# Flight_Control_Board.net
KiCad netlist of a schematic drawn in Altium Designer
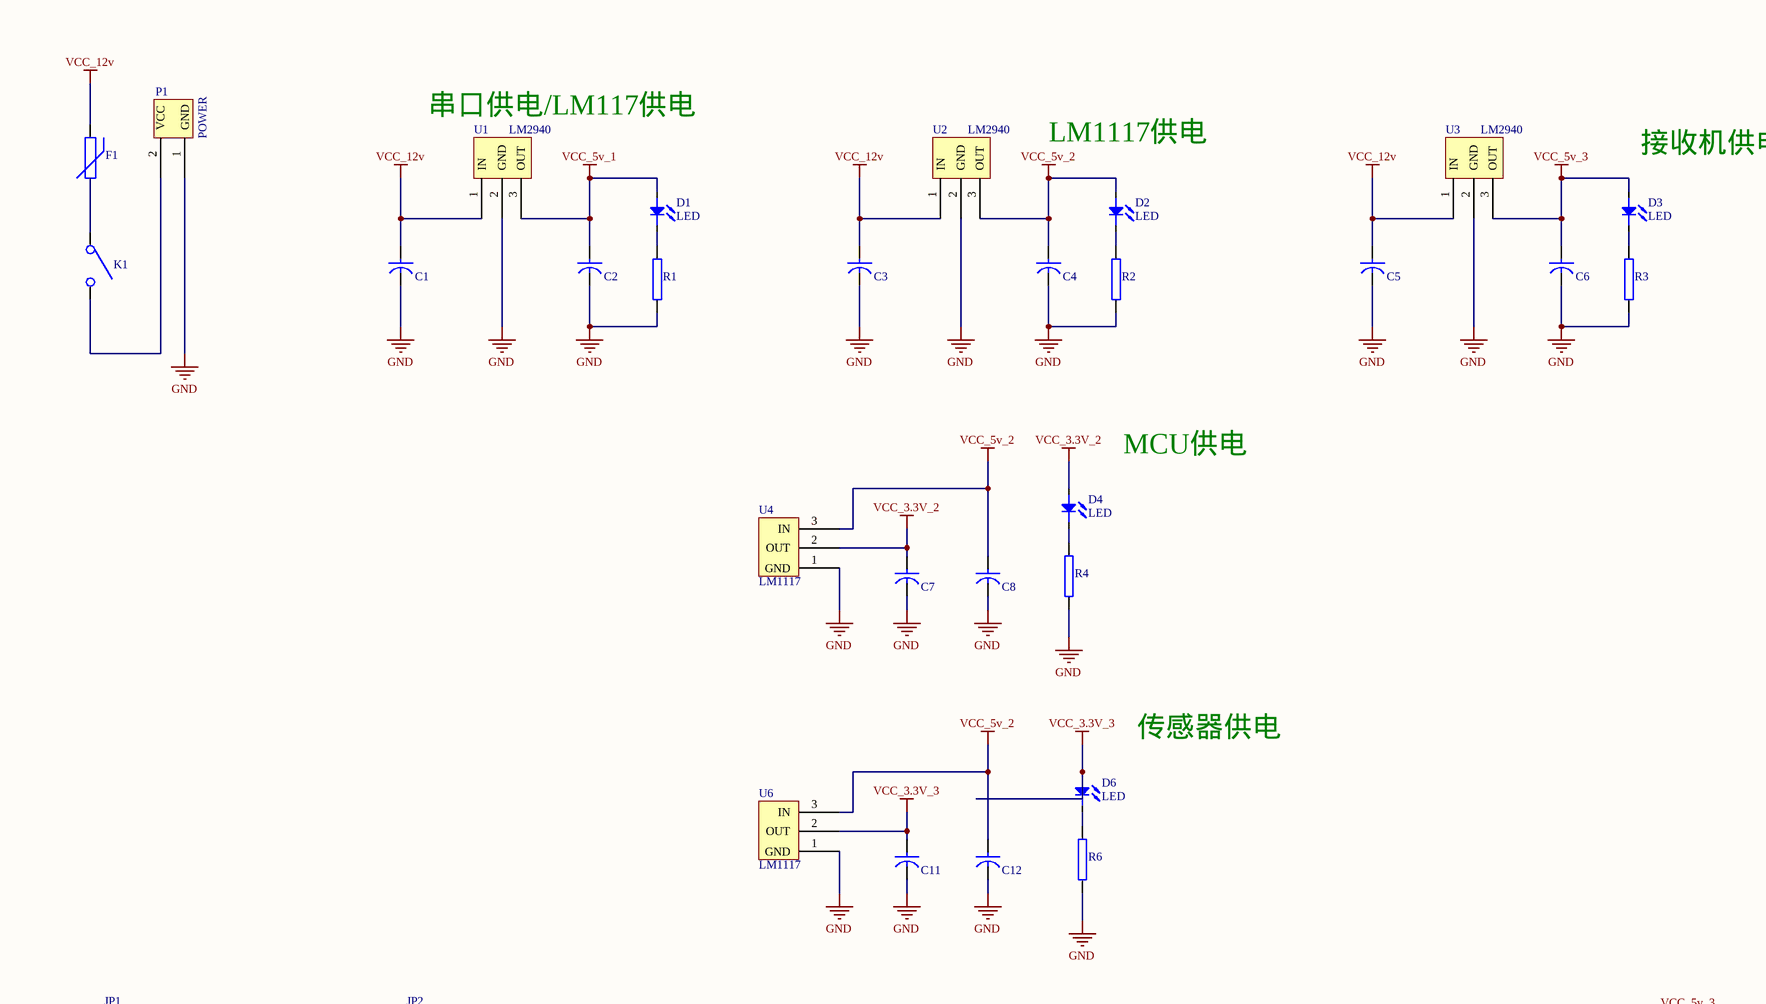
[diagram p0: Flight Control Board.SchDoc, top left]
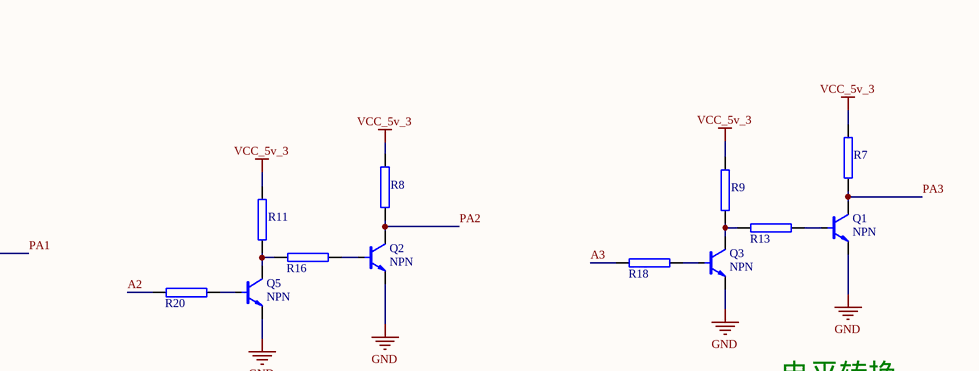
[diagram p1: Flight Control Board.SchDoc, top right]
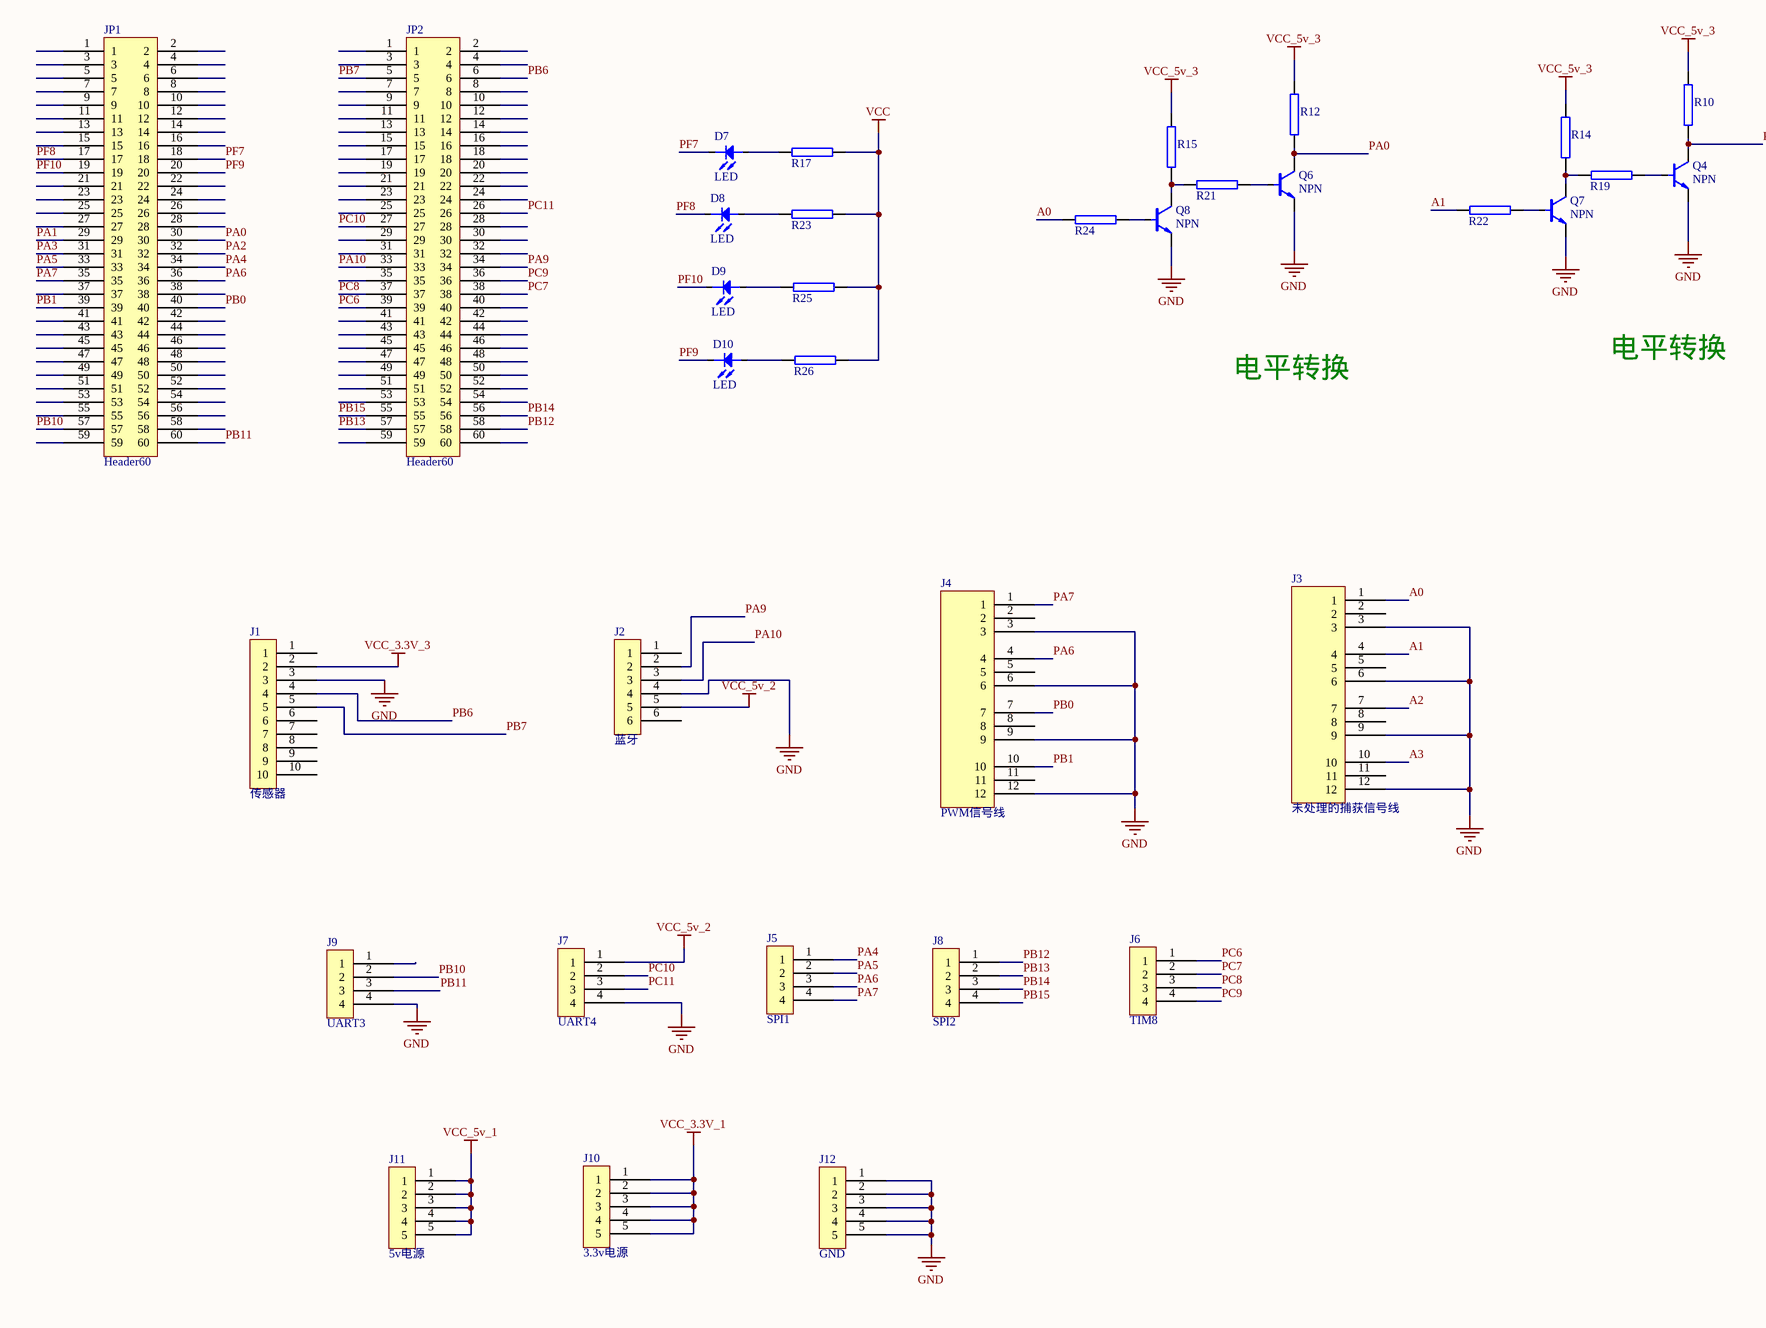
[diagram p2: Flight Control Board.SchDoc, bottom left]
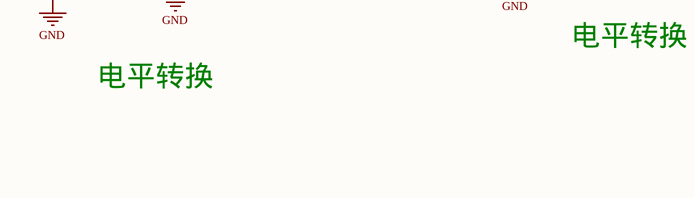
[diagram p3: Flight Control Board.SchDoc, bottom right]

(export (version "E")
  (design (tool "Eeschema 10.0.6"))
  (components
    (comp (ref "C1") (value "CAP_C") (footprint "CAP_C") (libsource (lib "Schlib1") (part "CAP_C")))
    (comp (ref "C2") (value "CAP_C") (footprint "CAP_C") (libsource (lib "Schlib1") (part "CAP_C")))
    (comp (ref "C3") (value "CAP_C") (footprint "CAP_C") (libsource (lib "Schlib1") (part "CAP_C")))
    (comp (ref "C4") (value "CAP_C") (footprint "CAP_C") (libsource (lib "Schlib1") (part "CAP_C")))
    (comp (ref "C5") (value "CAP_C") (footprint "CAP_C") (libsource (lib "Schlib1") (part "CAP_C")))
    (comp (ref "C6") (value "CAP_C") (footprint "CAP_C") (libsource (lib "Schlib1") (part "CAP_C")))
    (comp (ref "C7") (value "CAP_C") (footprint "CAP_C") (libsource (lib "Schlib1") (part "CAP_C")))
    (comp (ref "C8") (value "CAP_C") (footprint "CAP_C") (libsource (lib "Schlib1") (part "CAP_C")))
    (comp (ref "C11") (value "CAP_C") (footprint "CAP_C") (libsource (lib "Schlib1") (part "CAP_C")))
    (comp (ref "C12") (value "CAP_C") (footprint "CAP_C") (libsource (lib "Schlib1") (part "CAP_C")))
    (comp (ref "D1") (value "LED") (footprint "LED") (libsource (lib "Schlib1") (part "LED")))
    (comp (ref "D2") (value "LED") (footprint "LED") (libsource (lib "Schlib1") (part "LED")))
    (comp (ref "D3") (value "LED") (footprint "LED") (libsource (lib "Schlib1") (part "LED")))
    (comp (ref "D4") (value "LED") (footprint "LED") (libsource (lib "Schlib1") (part "LED")))
    (comp (ref "D6") (value "LED") (footprint "LED") (libsource (lib "Schlib1") (part "LED")))
    (comp (ref "D7") (value "LED") (footprint "LED") (libsource (lib "Schlib1") (part "LED")))
    (comp (ref "D8") (value "LED") (footprint "LED") (libsource (lib "Schlib1") (part "LED")))
    (comp (ref "D9") (value "LED") (footprint "LED") (libsource (lib "Schlib1") (part "LED")))
    (comp (ref "D10") (value "LED") (footprint "LED") (libsource (lib "Schlib1") (part "LED")))
    (comp (ref "F1") (value "FUSE") (footprint "FUSE") (libsource (lib "Schlib1") (part "FUSE")))
    (comp (ref "J1") (value "传感器") (footprint "Header10") (libsource (lib "Schlib1") (part "Header10")))
    (comp (ref "J2") (value "蓝牙") (footprint "Header6") (libsource (lib "Schlib1") (part "Header6")))
    (comp (ref "J3")
      (value "未处理的捕获信号线")
      (footprint "Header4*3")
      (libsource (lib "Schlib1") (part "Header4*3"))
    )
    (comp (ref "J4") (value "PWM信号线") (footprint "Header4*3") (libsource (lib "Schlib1") (part "Header4*3")))
    (comp (ref "J5") (value "SPI1") (footprint "Header4") (libsource (lib "Schlib1") (part "Header4")))
    (comp (ref "J6") (value "TIM8") (footprint "Header4") (libsource (lib "Schlib1") (part "Header4")))
    (comp (ref "J7") (value "UART4") (footprint "Header4") (libsource (lib "Schlib1") (part "Header4")))
    (comp (ref "J8") (value "SPI2") (footprint "Header4") (libsource (lib "Schlib1") (part "Header4")))
    (comp (ref "J9") (value "UART3") (footprint "Header4") (libsource (lib "Schlib1") (part "Header4")))
    (comp (ref "J10") (value "3.3v电源") (footprint "Header5") (libsource (lib "Schlib1") (part "Header5")))
    (comp (ref "J11") (value "5v电源") (footprint "Header5") (libsource (lib "Schlib1") (part "Header5")))
    (comp (ref "J12") (value "GND") (footprint "Header5") (libsource (lib "Schlib1") (part "Header5")))
    (comp (ref "JP1") (value "Header60") (footprint "Header60") (libsource (lib "Schlib1") (part "Header60")))
    (comp (ref "JP2") (value "Header60") (footprint "Header60") (libsource (lib "Schlib1") (part "Header60")))
    (comp (ref "K1") (value "KEY") (footprint "KEY") (libsource (lib "Schlib1") (part "KEY")))
    (comp (ref "P1") (value "POWER") (footprint "POWER") (libsource (lib "Schlib1") (part "POWER")))
    (comp (ref "Q1") (value "NPN") (footprint "NPN") (libsource (lib "Schlib1") (part "NPN")))
    (comp (ref "Q2") (value "NPN") (footprint "NPN") (libsource (lib "Schlib1") (part "NPN")))
    (comp (ref "Q3") (value "NPN") (footprint "NPN") (libsource (lib "Schlib1") (part "NPN")))
    (comp (ref "Q4") (value "NPN") (footprint "NPN") (libsource (lib "Schlib1") (part "NPN")))
    (comp (ref "Q5") (value "NPN") (footprint "NPN") (libsource (lib "Schlib1") (part "NPN")))
    (comp (ref "Q6") (value "NPN") (footprint "NPN") (libsource (lib "Schlib1") (part "NPN")))
    (comp (ref "Q7") (value "NPN") (footprint "NPN") (libsource (lib "Schlib1") (part "NPN")))
    (comp (ref "Q8") (value "NPN") (footprint "NPN") (libsource (lib "Schlib1") (part "NPN")))
    (comp (ref "R1") (value "RES") (footprint "LED") (libsource (lib "Schlib1") (part "RES")))
    (comp (ref "R2") (value "RES") (footprint "LED") (libsource (lib "Schlib1") (part "RES")))
    (comp (ref "R3") (value "RES") (footprint "LED") (libsource (lib "Schlib1") (part "RES")))
    (comp (ref "R4") (value "RES") (footprint "LED") (libsource (lib "Schlib1") (part "RES")))
    (comp (ref "R6") (value "RES") (footprint "LED") (libsource (lib "Schlib1") (part "RES")))
    (comp (ref "R7") (value "RES") (footprint "LED") (libsource (lib "Schlib1") (part "RES")))
    (comp (ref "R8") (value "RES") (footprint "LED") (libsource (lib "Schlib1") (part "RES")))
    (comp (ref "R9") (value "RES") (footprint "LED") (libsource (lib "Schlib1") (part "RES")))
    (comp (ref "R10") (value "RES") (footprint "LED") (libsource (lib "Schlib1") (part "RES")))
    (comp (ref "R11") (value "RES") (footprint "LED") (libsource (lib "Schlib1") (part "RES")))
    (comp (ref "R12") (value "RES") (footprint "LED") (libsource (lib "Schlib1") (part "RES")))
    (comp (ref "R13") (value "RES") (footprint "LED") (libsource (lib "Schlib1") (part "RES")))
    (comp (ref "R14") (value "RES") (footprint "LED") (libsource (lib "Schlib1") (part "RES")))
    (comp (ref "R15") (value "RES") (footprint "LED") (libsource (lib "Schlib1") (part "RES")))
    (comp (ref "R16") (value "RES") (footprint "LED") (libsource (lib "Schlib1") (part "RES")))
    (comp (ref "R17") (value "RES") (footprint "LED") (libsource (lib "Schlib1") (part "RES")))
    (comp (ref "R18") (value "RES") (footprint "LED") (libsource (lib "Schlib1") (part "RES")))
    (comp (ref "R19") (value "RES") (footprint "LED") (libsource (lib "Schlib1") (part "RES")))
    (comp (ref "R20") (value "RES") (footprint "LED") (libsource (lib "Schlib1") (part "RES")))
    (comp (ref "R21") (value "RES") (footprint "LED") (libsource (lib "Schlib1") (part "RES")))
    (comp (ref "R22") (value "RES") (footprint "LED") (libsource (lib "Schlib1") (part "RES")))
    (comp (ref "R23") (value "RES") (footprint "LED") (libsource (lib "Schlib1") (part "RES")))
    (comp (ref "R24") (value "RES") (footprint "LED") (libsource (lib "Schlib1") (part "RES")))
    (comp (ref "R25") (value "RES") (footprint "LED") (libsource (lib "Schlib1") (part "RES")))
    (comp (ref "R26") (value "RES") (footprint "LED") (libsource (lib "Schlib1") (part "RES")))
    (comp (ref "U1") (value "LM2940") (footprint "2940") (libsource (lib "Schlib1") (part "LM2940")))
    (comp (ref "U2") (value "LM2940") (footprint "2940") (libsource (lib "Schlib1") (part "LM2940")))
    (comp (ref "U3") (value "LM2940") (footprint "2940") (libsource (lib "Schlib1") (part "LM2940")))
    (comp (ref "U4") (value "LM1117") (footprint "1117") (libsource (lib "Schlib1") (part "LM1117")))
    (comp (ref "U6") (value "LM1117") (footprint "1117") (libsource (lib "Schlib1") (part "LM1117")))
  )
  (nets
    (net (code "1") (name "/A0") (class "Default")
      (node (ref "J3") (pin "1") (pinfunction "1_1") (pintype "passive"))
      (node (ref "R24") (pin "2") (pinfunction "2_2") (pintype "passive"))
    )
    (net (code "2") (name "/A1") (class "Default")
      (node (ref "J3") (pin "4") (pinfunction "4_4") (pintype "passive"))
      (node (ref "R22") (pin "2") (pinfunction "2_2") (pintype "passive"))
    )
    (net (code "3") (name "/A2") (class "Default")
      (node (ref "J3") (pin "7") (pinfunction "7_7") (pintype "passive"))
      (node (ref "R20") (pin "2") (pinfunction "2_2") (pintype "passive"))
    )
    (net (code "4") (name "/A3") (class "Default")
      (node (ref "J3") (pin "10") (pinfunction "10_10") (pintype "passive"))
      (node (ref "R18") (pin "2") (pinfunction "2_2") (pintype "passive"))
    )
    (net (code "5") (name "/PA0") (class "Default")
      (node (ref "JP1") (pin "30") (pinfunction "30_30") (pintype "passive"))
      (node (ref "Q6") (pin "C") (pinfunction "c_C") (pintype "passive"))
      (node (ref "R12") (pin "2") (pinfunction "2_2") (pintype "passive"))
    )
    (net (code "6") (name "/PA1") (class "Default")
      (node (ref "JP1") (pin "29") (pinfunction "29_29") (pintype "passive"))
      (node (ref "Q4") (pin "C") (pinfunction "c_C") (pintype "passive"))
      (node (ref "R10") (pin "2") (pinfunction "2_2") (pintype "passive"))
    )
    (net (code "7") (name "/PA2") (class "Default")
      (node (ref "JP1") (pin "32") (pinfunction "32_32") (pintype "passive"))
      (node (ref "Q2") (pin "C") (pinfunction "c_C") (pintype "passive"))
      (node (ref "R8") (pin "2") (pinfunction "2_2") (pintype "passive"))
    )
    (net (code "8") (name "/PA3") (class "Default")
      (node (ref "JP1") (pin "31") (pinfunction "31_31") (pintype "passive"))
      (node (ref "Q1") (pin "C") (pinfunction "c_C") (pintype "passive"))
      (node (ref "R7") (pin "2") (pinfunction "2_2") (pintype "passive"))
    )
    (net (code "9") (name "/PA4") (class "Default")
      (node (ref "J5") (pin "1") (pinfunction "1_1") (pintype "passive"))
      (node (ref "JP1") (pin "34") (pinfunction "34_34") (pintype "passive"))
    )
    (net (code "10") (name "/PA5") (class "Default")
      (node (ref "J5") (pin "2") (pinfunction "2_2") (pintype "passive"))
      (node (ref "JP1") (pin "33") (pinfunction "33_33") (pintype "passive"))
    )
    (net (code "11") (name "/PA6") (class "Default")
      (node (ref "J4") (pin "4") (pinfunction "4_4") (pintype "passive"))
      (node (ref "J5") (pin "3") (pinfunction "3_3") (pintype "passive"))
      (node (ref "JP1") (pin "36") (pinfunction "36_36") (pintype "passive"))
    )
    (net (code "12") (name "/PA7") (class "Default")
      (node (ref "J4") (pin "1") (pinfunction "1_1") (pintype "passive"))
      (node (ref "J5") (pin "4") (pinfunction "4_4") (pintype "passive"))
      (node (ref "JP1") (pin "35") (pinfunction "35_35") (pintype "passive"))
    )
    (net (code "13") (name "/PA9") (class "Default")
      (node (ref "J2") (pin "2") (pinfunction "2_2") (pintype "passive"))
      (node (ref "JP2") (pin "34") (pinfunction "34_34") (pintype "passive"))
    )
    (net (code "14") (name "/PA10") (class "Default")
      (node (ref "J2") (pin "3") (pinfunction "3_3") (pintype "passive"))
      (node (ref "JP2") (pin "33") (pinfunction "33_33") (pintype "passive"))
    )
    (net (code "15") (name "/PB0") (class "Default")
      (node (ref "J4") (pin "7") (pinfunction "7_7") (pintype "passive"))
      (node (ref "JP1") (pin "40") (pinfunction "40_40") (pintype "passive"))
    )
    (net (code "16") (name "/PB1") (class "Default")
      (node (ref "J4") (pin "10") (pinfunction "10_10") (pintype "passive"))
      (node (ref "JP1") (pin "39") (pinfunction "39_39") (pintype "passive"))
    )
    (net (code "17") (name "/PB6") (class "Default")
      (node (ref "J1") (pin "4") (pinfunction "4_4") (pintype "passive"))
      (node (ref "JP2") (pin "6") (pinfunction "6_6") (pintype "passive"))
    )
    (net (code "18") (name "/PB7") (class "Default")
      (node (ref "J1") (pin "5") (pinfunction "5_5") (pintype "passive"))
      (node (ref "JP2") (pin "5") (pinfunction "5_5") (pintype "passive"))
    )
    (net (code "19") (name "/PB10") (class "Default")
      (node (ref "J9") (pin "2") (pinfunction "2_2") (pintype "passive"))
      (node (ref "JP1") (pin "57") (pinfunction "57_57") (pintype "passive"))
    )
    (net (code "20") (name "/PB11") (class "Default")
      (node (ref "J9") (pin "3") (pinfunction "3_3") (pintype "passive"))
      (node (ref "JP1") (pin "60") (pinfunction "60_60") (pintype "passive"))
    )
    (net (code "21") (name "/PB12") (class "Default")
      (node (ref "J8") (pin "1") (pinfunction "1_1") (pintype "passive"))
      (node (ref "JP2") (pin "58") (pinfunction "58_58") (pintype "passive"))
    )
    (net (code "22") (name "/PB13") (class "Default")
      (node (ref "J8") (pin "2") (pinfunction "2_2") (pintype "passive"))
      (node (ref "JP2") (pin "57") (pinfunction "57_57") (pintype "passive"))
    )
    (net (code "23") (name "/PB14") (class "Default")
      (node (ref "J8") (pin "3") (pinfunction "3_3") (pintype "passive"))
      (node (ref "JP2") (pin "56") (pinfunction "56_56") (pintype "passive"))
    )
    (net (code "24") (name "/PB15") (class "Default")
      (node (ref "J8") (pin "4") (pinfunction "4_4") (pintype "passive"))
      (node (ref "JP2") (pin "55") (pinfunction "55_55") (pintype "passive"))
    )
    (net (code "25") (name "/PC6") (class "Default")
      (node (ref "J6") (pin "1") (pinfunction "1_1") (pintype "passive"))
      (node (ref "JP2") (pin "39") (pinfunction "39_39") (pintype "passive"))
    )
    (net (code "26") (name "/PC7") (class "Default")
      (node (ref "J6") (pin "2") (pinfunction "2_2") (pintype "passive"))
      (node (ref "JP2") (pin "38") (pinfunction "38_38") (pintype "passive"))
    )
    (net (code "27") (name "/PC8") (class "Default")
      (node (ref "J6") (pin "3") (pinfunction "3_3") (pintype "passive"))
      (node (ref "JP2") (pin "37") (pinfunction "37_37") (pintype "passive"))
    )
    (net (code "28") (name "/PC9") (class "Default")
      (node (ref "J6") (pin "4") (pinfunction "4_4") (pintype "passive"))
      (node (ref "JP2") (pin "36") (pinfunction "36_36") (pintype "passive"))
    )
    (net (code "29") (name "/PC10") (class "Default")
      (node (ref "J7") (pin "2") (pinfunction "2_2") (pintype "passive"))
      (node (ref "JP2") (pin "27") (pinfunction "27_27") (pintype "passive"))
    )
    (net (code "30") (name "/PC11") (class "Default")
      (node (ref "J7") (pin "3") (pinfunction "3_3") (pintype "passive"))
      (node (ref "JP2") (pin "26") (pinfunction "26_26") (pintype "passive"))
    )
    (net (code "31") (name "/PF7") (class "Default")
      (node (ref "D7") (pin "2") (pinfunction "2_2") (pintype "passive"))
      (node (ref "JP1") (pin "18") (pinfunction "18_18") (pintype "passive"))
    )
    (net (code "32") (name "/PF8") (class "Default")
      (node (ref "D8") (pin "2") (pinfunction "2_2") (pintype "passive"))
      (node (ref "JP1") (pin "17") (pinfunction "17_17") (pintype "passive"))
    )
    (net (code "33") (name "/PF9") (class "Default")
      (node (ref "D10") (pin "2") (pinfunction "2_2") (pintype "passive"))
      (node (ref "JP1") (pin "20") (pinfunction "20_20") (pintype "passive"))
    )
    (net (code "34") (name "/PF10") (class "Default")
      (node (ref "D9") (pin "2") (pinfunction "2_2") (pintype "passive"))
      (node (ref "JP1") (pin "19") (pinfunction "19_19") (pintype "passive"))
    )
    (net (code "35") (name "GND") (class "Default")
      (node (ref "C1") (pin "2") (pinfunction "2_2") (pintype "passive"))
      (node (ref "C11") (pin "2") (pinfunction "2_2") (pintype "passive"))
      (node (ref "C12") (pin "2") (pinfunction "2_2") (pintype "passive"))
      (node (ref "C2") (pin "2") (pinfunction "2_2") (pintype "passive"))
      (node (ref "C3") (pin "2") (pinfunction "2_2") (pintype "passive"))
      (node (ref "C4") (pin "2") (pinfunction "2_2") (pintype "passive"))
      (node (ref "C5") (pin "2") (pinfunction "2_2") (pintype "passive"))
      (node (ref "C6") (pin "2") (pinfunction "2_2") (pintype "passive"))
      (node (ref "C7") (pin "2") (pinfunction "2_2") (pintype "passive"))
      (node (ref "C8") (pin "2") (pinfunction "2_2") (pintype "passive"))
      (node (ref "J1") (pin "3") (pinfunction "3_3") (pintype "passive"))
      (node (ref "J12") (pin "1") (pinfunction "1_1") (pintype "passive"))
      (node (ref "J12") (pin "2") (pinfunction "2_2") (pintype "passive"))
      (node (ref "J12") (pin "3") (pinfunction "3_3") (pintype "passive"))
      (node (ref "J12") (pin "4") (pinfunction "4_4") (pintype "passive"))
      (node (ref "J12") (pin "5") (pinfunction "5_5") (pintype "passive"))
      (node (ref "J2") (pin "4") (pinfunction "4_4") (pintype "passive"))
      (node (ref "J3") (pin "12") (pinfunction "12_12") (pintype "passive"))
      (node (ref "J3") (pin "3") (pinfunction "3_3") (pintype "passive"))
      (node (ref "J3") (pin "6") (pinfunction "6_6") (pintype "passive"))
      (node (ref "J3") (pin "9") (pinfunction "9_9") (pintype "passive"))
      (node (ref "J4") (pin "12") (pinfunction "12_12") (pintype "passive"))
      (node (ref "J4") (pin "3") (pinfunction "3_3") (pintype "passive"))
      (node (ref "J4") (pin "6") (pinfunction "6_6") (pintype "passive"))
      (node (ref "J4") (pin "9") (pinfunction "9_9") (pintype "passive"))
      (node (ref "J7") (pin "4") (pinfunction "4_4") (pintype "passive"))
      (node (ref "J9") (pin "4") (pinfunction "4_4") (pintype "passive"))
      (node (ref "P1") (pin "1") (pinfunction "GND_1") (pintype "passive"))
      (node (ref "Q1") (pin "E") (pinfunction "e_E") (pintype "passive"))
      (node (ref "Q2") (pin "E") (pinfunction "e_E") (pintype "passive"))
      (node (ref "Q3") (pin "E") (pinfunction "e_E") (pintype "passive"))
      (node (ref "Q4") (pin "E") (pinfunction "e_E") (pintype "passive"))
      (node (ref "Q5") (pin "E") (pinfunction "e_E") (pintype "passive"))
      (node (ref "Q6") (pin "E") (pinfunction "e_E") (pintype "passive"))
      (node (ref "Q7") (pin "E") (pinfunction "e_E") (pintype "passive"))
      (node (ref "Q8") (pin "E") (pinfunction "e_E") (pintype "passive"))
      (node (ref "R1") (pin "1") (pinfunction "1_1") (pintype "passive"))
      (node (ref "R2") (pin "1") (pinfunction "1_1") (pintype "passive"))
      (node (ref "R3") (pin "1") (pinfunction "1_1") (pintype "passive"))
      (node (ref "R4") (pin "1") (pinfunction "1_1") (pintype "passive"))
      (node (ref "R6") (pin "1") (pinfunction "1_1") (pintype "passive"))
      (node (ref "U1") (pin "2") (pinfunction "GND_2") (pintype "passive"))
      (node (ref "U2") (pin "2") (pinfunction "GND_2") (pintype "passive"))
      (node (ref "U3") (pin "2") (pinfunction "GND_2") (pintype "passive"))
      (node (ref "U4") (pin "1") (pinfunction "GND_1") (pintype "passive"))
      (node (ref "U6") (pin "1") (pinfunction "GND_1") (pintype "passive"))
    )
    (net (code "36") (name "Net-(D1-Pad2)") (class "Default")
      (node (ref "D1") (pin "2") (pinfunction "2_2") (pintype "passive"))
      (node (ref "R1") (pin "2") (pinfunction "2_2") (pintype "passive"))
    )
    (net (code "37") (name "Net-(D2-Pad2)") (class "Default")
      (node (ref "D2") (pin "2") (pinfunction "2_2") (pintype "passive"))
      (node (ref "R2") (pin "2") (pinfunction "2_2") (pintype "passive"))
    )
    (net (code "38") (name "Net-(D3-Pad2)") (class "Default")
      (node (ref "D3") (pin "2") (pinfunction "2_2") (pintype "passive"))
      (node (ref "R3") (pin "2") (pinfunction "2_2") (pintype "passive"))
    )
    (net (code "39") (name "Net-(D4-Pad2)") (class "Default")
      (node (ref "D4") (pin "2") (pinfunction "2_2") (pintype "passive"))
      (node (ref "R4") (pin "2") (pinfunction "2_2") (pintype "passive"))
    )
    (net (code "40") (name "Net-(D6-Pad2)") (class "Default")
      (node (ref "D6") (pin "2") (pinfunction "2_2") (pintype "passive"))
      (node (ref "R6") (pin "2") (pinfunction "2_2") (pintype "passive"))
    )
    (net (code "41") (name "Net-(D7-Pad1)") (class "Default")
      (node (ref "D7") (pin "1") (pinfunction "1_1") (pintype "passive"))
      (node (ref "R17") (pin "2") (pinfunction "2_2") (pintype "passive"))
    )
    (net (code "42") (name "Net-(D8-Pad1)") (class "Default")
      (node (ref "D8") (pin "1") (pinfunction "1_1") (pintype "passive"))
      (node (ref "R23") (pin "2") (pinfunction "2_2") (pintype "passive"))
    )
    (net (code "43") (name "Net-(D9-Pad1)") (class "Default")
      (node (ref "D9") (pin "1") (pinfunction "1_1") (pintype "passive"))
      (node (ref "R25") (pin "2") (pinfunction "2_2") (pintype "passive"))
    )
    (net (code "44") (name "Net-(D10-Pad1)") (class "Default")
      (node (ref "D10") (pin "1") (pinfunction "1_1") (pintype "passive"))
      (node (ref "R26") (pin "2") (pinfunction "2_2") (pintype "passive"))
    )
    (net (code "45") (name "Net-(F1-Pad2)") (class "Default")
      (node (ref "F1") (pin "2") (pinfunction "2_2") (pintype "passive"))
      (node (ref "K1") (pin "1") (pinfunction "1_1") (pintype "passive"))
    )
    (net (code "46") (name "Net-(P1-VCC)") (class "Default")
      (node (ref "K1") (pin "2") (pinfunction "2_2") (pintype "passive"))
      (node (ref "P1") (pin "2") (pinfunction "VCC_2") (pintype "passive"))
    )
    (net (code "47") (name "Net-(Q1-b)") (class "Default")
      (node (ref "Q1") (pin "B") (pinfunction "b_B") (pintype "passive"))
      (node (ref "R13") (pin "2") (pinfunction "2_2") (pintype "passive"))
    )
    (net (code "48") (name "Net-(Q2-b)") (class "Default")
      (node (ref "Q2") (pin "B") (pinfunction "b_B") (pintype "passive"))
      (node (ref "R16") (pin "2") (pinfunction "2_2") (pintype "passive"))
    )
    (net (code "49") (name "Net-(Q3-b)") (class "Default")
      (node (ref "Q3") (pin "B") (pinfunction "b_B") (pintype "passive"))
      (node (ref "R18") (pin "1") (pinfunction "1_1") (pintype "passive"))
    )
    (net (code "50") (name "Net-(Q3-c)") (class "Default")
      (node (ref "Q3") (pin "C") (pinfunction "c_C") (pintype "passive"))
      (node (ref "R13") (pin "1") (pinfunction "1_1") (pintype "passive"))
      (node (ref "R9") (pin "2") (pinfunction "2_2") (pintype "passive"))
    )
    (net (code "51") (name "Net-(Q4-b)") (class "Default")
      (node (ref "Q4") (pin "B") (pinfunction "b_B") (pintype "passive"))
      (node (ref "R19") (pin "2") (pinfunction "2_2") (pintype "passive"))
    )
    (net (code "52") (name "Net-(Q5-b)") (class "Default")
      (node (ref "Q5") (pin "B") (pinfunction "b_B") (pintype "passive"))
      (node (ref "R20") (pin "1") (pinfunction "1_1") (pintype "passive"))
    )
    (net (code "53") (name "Net-(Q5-c)") (class "Default")
      (node (ref "Q5") (pin "C") (pinfunction "c_C") (pintype "passive"))
      (node (ref "R11") (pin "2") (pinfunction "2_2") (pintype "passive"))
      (node (ref "R16") (pin "1") (pinfunction "1_1") (pintype "passive"))
    )
    (net (code "54") (name "Net-(Q6-b)") (class "Default")
      (node (ref "Q6") (pin "B") (pinfunction "b_B") (pintype "passive"))
      (node (ref "R21") (pin "2") (pinfunction "2_2") (pintype "passive"))
    )
    (net (code "55") (name "Net-(Q7-b)") (class "Default")
      (node (ref "Q7") (pin "B") (pinfunction "b_B") (pintype "passive"))
      (node (ref "R22") (pin "1") (pinfunction "1_1") (pintype "passive"))
    )
    (net (code "56") (name "Net-(Q7-c)") (class "Default")
      (node (ref "Q7") (pin "C") (pinfunction "c_C") (pintype "passive"))
      (node (ref "R14") (pin "2") (pinfunction "2_2") (pintype "passive"))
      (node (ref "R19") (pin "1") (pinfunction "1_1") (pintype "passive"))
    )
    (net (code "57") (name "Net-(Q8-b)") (class "Default")
      (node (ref "Q8") (pin "B") (pinfunction "b_B") (pintype "passive"))
      (node (ref "R24") (pin "1") (pinfunction "1_1") (pintype "passive"))
    )
    (net (code "58") (name "Net-(Q8-c)") (class "Default")
      (node (ref "Q8") (pin "C") (pinfunction "c_C") (pintype "passive"))
      (node (ref "R15") (pin "2") (pinfunction "2_2") (pintype "passive"))
      (node (ref "R21") (pin "1") (pinfunction "1_1") (pintype "passive"))
    )
    (net (code "59") (name "VCC") (class "Default")
      (node (ref "R17") (pin "1") (pinfunction "1_1") (pintype "passive"))
      (node (ref "R23") (pin "1") (pinfunction "1_1") (pintype "passive"))
      (node (ref "R25") (pin "1") (pinfunction "1_1") (pintype "passive"))
      (node (ref "R26") (pin "1") (pinfunction "1_1") (pintype "passive"))
    )
    (net (code "60") (name "VCC_3.3V_1") (class "Default")
      (node (ref "J10") (pin "1") (pinfunction "1_1") (pintype "passive"))
      (node (ref "J10") (pin "2") (pinfunction "2_2") (pintype "passive"))
      (node (ref "J10") (pin "3") (pinfunction "3_3") (pintype "passive"))
      (node (ref "J10") (pin "4") (pinfunction "4_4") (pintype "passive"))
      (node (ref "J10") (pin "5") (pinfunction "5_5") (pintype "passive"))
    )
    (net (code "61") (name "VCC_3.3V_2") (class "Default")
      (node (ref "C7") (pin "1") (pinfunction "1_1") (pintype "passive"))
      (node (ref "D4") (pin "1") (pinfunction "1_1") (pintype "passive"))
      (node (ref "U4") (pin "2") (pinfunction "OUT_2") (pintype "passive"))
    )
    (net (code "62") (name "VCC_3.3V_3") (class "Default")
      (node (ref "C11") (pin "1") (pinfunction "1_1") (pintype "passive"))
      (node (ref "D6") (pin "1") (pinfunction "1_1") (pintype "passive"))
      (node (ref "J1") (pin "2") (pinfunction "2_2") (pintype "passive"))
      (node (ref "U6") (pin "2") (pinfunction "OUT_2") (pintype "passive"))
    )
    (net (code "63") (name "VCC_5v_1") (class "Default")
      (node (ref "C2") (pin "1") (pinfunction "1_1") (pintype "passive"))
      (node (ref "D1") (pin "1") (pinfunction "1_1") (pintype "passive"))
      (node (ref "J11") (pin "1") (pinfunction "1_1") (pintype "passive"))
      (node (ref "J11") (pin "2") (pinfunction "2_2") (pintype "passive"))
      (node (ref "J11") (pin "3") (pinfunction "3_3") (pintype "passive"))
      (node (ref "J11") (pin "4") (pinfunction "4_4") (pintype "passive"))
      (node (ref "J11") (pin "5") (pinfunction "5_5") (pintype "passive"))
      (node (ref "U1") (pin "3") (pinfunction "OUT_3") (pintype "passive"))
    )
    (net (code "64") (name "VCC_5v_2") (class "Default")
      (node (ref "C12") (pin "1") (pinfunction "1_1") (pintype "passive"))
      (node (ref "C4") (pin "1") (pinfunction "1_1") (pintype "passive"))
      (node (ref "C8") (pin "1") (pinfunction "1_1") (pintype "passive"))
      (node (ref "D2") (pin "1") (pinfunction "1_1") (pintype "passive"))
      (node (ref "J2") (pin "5") (pinfunction "5_5") (pintype "passive"))
      (node (ref "J7") (pin "1") (pinfunction "1_1") (pintype "passive"))
      (node (ref "U2") (pin "3") (pinfunction "OUT_3") (pintype "passive"))
      (node (ref "U4") (pin "3") (pinfunction "IN_3") (pintype "passive"))
      (node (ref "U6") (pin "3") (pinfunction "IN_3") (pintype "passive"))
    )
    (net (code "65") (name "VCC_5v_3") (class "Default")
      (node (ref "C6") (pin "1") (pinfunction "1_1") (pintype "passive"))
      (node (ref "D3") (pin "1") (pinfunction "1_1") (pintype "passive"))
      (node (ref "R10") (pin "1") (pinfunction "1_1") (pintype "passive"))
      (node (ref "R11") (pin "1") (pinfunction "1_1") (pintype "passive"))
      (node (ref "R12") (pin "1") (pinfunction "1_1") (pintype "passive"))
      (node (ref "R14") (pin "1") (pinfunction "1_1") (pintype "passive"))
      (node (ref "R15") (pin "1") (pinfunction "1_1") (pintype "passive"))
      (node (ref "R7") (pin "1") (pinfunction "1_1") (pintype "passive"))
      (node (ref "R8") (pin "1") (pinfunction "1_1") (pintype "passive"))
      (node (ref "R9") (pin "1") (pinfunction "1_1") (pintype "passive"))
      (node (ref "U3") (pin "3") (pinfunction "OUT_3") (pintype "passive"))
    )
    (net (code "66") (name "VCC_12v") (class "Default")
      (node (ref "C1") (pin "1") (pinfunction "1_1") (pintype "passive"))
      (node (ref "C3") (pin "1") (pinfunction "1_1") (pintype "passive"))
      (node (ref "C5") (pin "1") (pinfunction "1_1") (pintype "passive"))
      (node (ref "F1") (pin "1") (pinfunction "1_1") (pintype "passive"))
      (node (ref "U1") (pin "1") (pinfunction "IN_1") (pintype "passive"))
      (node (ref "U2") (pin "1") (pinfunction "IN_1") (pintype "passive"))
      (node (ref "U3") (pin "1") (pinfunction "IN_1") (pintype "passive"))
    )
    (net (code "67") (name "unconnected-(J1-Pad1)") (class "Default")
      (node (ref "J1") (pin "1") (pinfunction "1_1") (pintype "passive"))
    )
    (net (code "68") (name "unconnected-(J1-Pad6)") (class "Default")
      (node (ref "J1") (pin "6") (pinfunction "6_6") (pintype "passive"))
    )
    (net (code "69") (name "unconnected-(J1-Pad7)") (class "Default")
      (node (ref "J1") (pin "7") (pinfunction "7_7") (pintype "passive"))
    )
    (net (code "70") (name "unconnected-(J1-Pad8)") (class "Default")
      (node (ref "J1") (pin "8") (pinfunction "8_8") (pintype "passive"))
    )
    (net (code "71") (name "unconnected-(J1-Pad9)") (class "Default")
      (node (ref "J1") (pin "9") (pinfunction "9_9") (pintype "passive"))
    )
    (net (code "72") (name "unconnected-(J1-Pad10)") (class "Default")
      (node (ref "J1") (pin "10") (pinfunction "10_10") (pintype "passive"))
    )
    (net (code "73") (name "unconnected-(J2-Pad1)") (class "Default")
      (node (ref "J2") (pin "1") (pinfunction "1_1") (pintype "passive"))
    )
    (net (code "74") (name "unconnected-(J2-Pad6)") (class "Default")
      (node (ref "J2") (pin "6") (pinfunction "6_6") (pintype "passive"))
    )
    (net (code "75") (name "unconnected-(J3-Pad2)") (class "Default")
      (node (ref "J3") (pin "2") (pinfunction "2_2") (pintype "passive"))
    )
    (net (code "76") (name "unconnected-(J3-Pad5)") (class "Default")
      (node (ref "J3") (pin "5") (pinfunction "5_5") (pintype "passive"))
    )
    (net (code "77") (name "unconnected-(J3-Pad8)") (class "Default")
      (node (ref "J3") (pin "8") (pinfunction "8_8") (pintype "passive"))
    )
    (net (code "78") (name "unconnected-(J3-Pad11)") (class "Default")
      (node (ref "J3") (pin "11") (pinfunction "11_11") (pintype "passive"))
    )
    (net (code "79") (name "unconnected-(J4-Pad2)") (class "Default")
      (node (ref "J4") (pin "2") (pinfunction "2_2") (pintype "passive"))
    )
    (net (code "80") (name "unconnected-(J4-Pad5)") (class "Default")
      (node (ref "J4") (pin "5") (pinfunction "5_5") (pintype "passive"))
    )
    (net (code "81") (name "unconnected-(J4-Pad8)") (class "Default")
      (node (ref "J4") (pin "8") (pinfunction "8_8") (pintype "passive"))
    )
    (net (code "82") (name "unconnected-(J4-Pad11)") (class "Default")
      (node (ref "J4") (pin "11") (pinfunction "11_11") (pintype "passive"))
    )
    (net (code "83") (name "unconnected-(J9-Pad1)") (class "Default")
      (node (ref "J9") (pin "1") (pinfunction "1_1") (pintype "passive"))
    )
    (net (code "84") (name "unconnected-(JP1-Pad1)") (class "Default")
      (node (ref "JP1") (pin "1") (pinfunction "1_1") (pintype "passive"))
    )
    (net (code "85") (name "unconnected-(JP1-Pad2)") (class "Default")
      (node (ref "JP1") (pin "2") (pinfunction "2_2") (pintype "passive"))
    )
    (net (code "86") (name "unconnected-(JP1-Pad3)") (class "Default")
      (node (ref "JP1") (pin "3") (pinfunction "3_3") (pintype "passive"))
    )
    (net (code "87") (name "unconnected-(JP1-Pad4)") (class "Default")
      (node (ref "JP1") (pin "4") (pinfunction "4_4") (pintype "passive"))
    )
    (net (code "88") (name "unconnected-(JP1-Pad5)") (class "Default")
      (node (ref "JP1") (pin "5") (pinfunction "5_5") (pintype "passive"))
    )
    (net (code "89") (name "unconnected-(JP1-Pad6)") (class "Default")
      (node (ref "JP1") (pin "6") (pinfunction "6_6") (pintype "passive"))
    )
    (net (code "90") (name "unconnected-(JP1-Pad7)") (class "Default")
      (node (ref "JP1") (pin "7") (pinfunction "7_7") (pintype "passive"))
    )
    (net (code "91") (name "unconnected-(JP1-Pad8)") (class "Default")
      (node (ref "JP1") (pin "8") (pinfunction "8_8") (pintype "passive"))
    )
    (net (code "92") (name "unconnected-(JP1-Pad9)") (class "Default")
      (node (ref "JP1") (pin "9") (pinfunction "9_9") (pintype "passive"))
    )
    (net (code "93") (name "unconnected-(JP1-Pad10)") (class "Default")
      (node (ref "JP1") (pin "10") (pinfunction "10_10") (pintype "passive"))
    )
    (net (code "94") (name "unconnected-(JP1-Pad11)") (class "Default")
      (node (ref "JP1") (pin "11") (pinfunction "11_11") (pintype "passive"))
    )
    (net (code "95") (name "unconnected-(JP1-Pad12)") (class "Default")
      (node (ref "JP1") (pin "12") (pinfunction "12_12") (pintype "passive"))
    )
    (net (code "96") (name "unconnected-(JP1-Pad13)") (class "Default")
      (node (ref "JP1") (pin "13") (pinfunction "13_13") (pintype "passive"))
    )
    (net (code "97") (name "unconnected-(JP1-Pad14)") (class "Default")
      (node (ref "JP1") (pin "14") (pinfunction "14_14") (pintype "passive"))
    )
    (net (code "98") (name "unconnected-(JP1-Pad15)") (class "Default")
      (node (ref "JP1") (pin "15") (pinfunction "15_15") (pintype "passive"))
    )
    (net (code "99") (name "unconnected-(JP1-Pad16)") (class "Default")
      (node (ref "JP1") (pin "16") (pinfunction "16_16") (pintype "passive"))
    )
    (net (code "100") (name "unconnected-(JP1-Pad21)") (class "Default")
      (node (ref "JP1") (pin "21") (pinfunction "21_21") (pintype "passive"))
    )
    (net (code "101") (name "unconnected-(JP1-Pad22)") (class "Default")
      (node (ref "JP1") (pin "22") (pinfunction "22_22") (pintype "passive"))
    )
    (net (code "102") (name "unconnected-(JP1-Pad23)") (class "Default")
      (node (ref "JP1") (pin "23") (pinfunction "23_23") (pintype "passive"))
    )
    (net (code "103") (name "unconnected-(JP1-Pad24)") (class "Default")
      (node (ref "JP1") (pin "24") (pinfunction "24_24") (pintype "passive"))
    )
    (net (code "104") (name "unconnected-(JP1-Pad25)") (class "Default")
      (node (ref "JP1") (pin "25") (pinfunction "25_25") (pintype "passive"))
    )
    (net (code "105") (name "unconnected-(JP1-Pad26)") (class "Default")
      (node (ref "JP1") (pin "26") (pinfunction "26_26") (pintype "passive"))
    )
    (net (code "106") (name "unconnected-(JP1-Pad27)") (class "Default")
      (node (ref "JP1") (pin "27") (pinfunction "27_27") (pintype "passive"))
    )
    (net (code "107") (name "unconnected-(JP1-Pad28)") (class "Default")
      (node (ref "JP1") (pin "28") (pinfunction "28_28") (pintype "passive"))
    )
    (net (code "108") (name "unconnected-(JP1-Pad37)") (class "Default")
      (node (ref "JP1") (pin "37") (pinfunction "37_37") (pintype "passive"))
    )
    (net (code "109") (name "unconnected-(JP1-Pad38)") (class "Default")
      (node (ref "JP1") (pin "38") (pinfunction "38_38") (pintype "passive"))
    )
    (net (code "110") (name "unconnected-(JP1-Pad41)") (class "Default")
      (node (ref "JP1") (pin "41") (pinfunction "41_41") (pintype "passive"))
    )
    (net (code "111") (name "unconnected-(JP1-Pad42)") (class "Default")
      (node (ref "JP1") (pin "42") (pinfunction "42_42") (pintype "passive"))
    )
    (net (code "112") (name "unconnected-(JP1-Pad43)") (class "Default")
      (node (ref "JP1") (pin "43") (pinfunction "43_43") (pintype "passive"))
    )
    (net (code "113") (name "unconnected-(JP1-Pad44)") (class "Default")
      (node (ref "JP1") (pin "44") (pinfunction "44_44") (pintype "passive"))
    )
    (net (code "114") (name "unconnected-(JP1-Pad45)") (class "Default")
      (node (ref "JP1") (pin "45") (pinfunction "45_45") (pintype "passive"))
    )
    (net (code "115") (name "unconnected-(JP1-Pad46)") (class "Default")
      (node (ref "JP1") (pin "46") (pinfunction "46_46") (pintype "passive"))
    )
    (net (code "116") (name "unconnected-(JP1-Pad47)") (class "Default")
      (node (ref "JP1") (pin "47") (pinfunction "47_47") (pintype "passive"))
    )
    (net (code "117") (name "unconnected-(JP1-Pad48)") (class "Default")
      (node (ref "JP1") (pin "48") (pinfunction "48_48") (pintype "passive"))
    )
    (net (code "118") (name "unconnected-(JP1-Pad49)") (class "Default")
      (node (ref "JP1") (pin "49") (pinfunction "49_49") (pintype "passive"))
    )
    (net (code "119") (name "unconnected-(JP1-Pad50)") (class "Default")
      (node (ref "JP1") (pin "50") (pinfunction "50_50") (pintype "passive"))
    )
    (net (code "120") (name "unconnected-(JP1-Pad51)") (class "Default")
      (node (ref "JP1") (pin "51") (pinfunction "51_51") (pintype "passive"))
    )
    (net (code "121") (name "unconnected-(JP1-Pad52)") (class "Default")
      (node (ref "JP1") (pin "52") (pinfunction "52_52") (pintype "passive"))
    )
    (net (code "122") (name "unconnected-(JP1-Pad53)") (class "Default")
      (node (ref "JP1") (pin "53") (pinfunction "53_53") (pintype "passive"))
    )
    (net (code "123") (name "unconnected-(JP1-Pad54)") (class "Default")
      (node (ref "JP1") (pin "54") (pinfunction "54_54") (pintype "passive"))
    )
    (net (code "124") (name "unconnected-(JP1-Pad55)") (class "Default")
      (node (ref "JP1") (pin "55") (pinfunction "55_55") (pintype "passive"))
    )
    (net (code "125") (name "unconnected-(JP1-Pad56)") (class "Default")
      (node (ref "JP1") (pin "56") (pinfunction "56_56") (pintype "passive"))
    )
    (net (code "126") (name "unconnected-(JP1-Pad58)") (class "Default")
      (node (ref "JP1") (pin "58") (pinfunction "58_58") (pintype "passive"))
    )
    (net (code "127") (name "unconnected-(JP1-Pad59)") (class "Default")
      (node (ref "JP1") (pin "59") (pinfunction "59_59") (pintype "passive"))
    )
    (net (code "128") (name "unconnected-(JP2-Pad1)") (class "Default")
      (node (ref "JP2") (pin "1") (pinfunction "1_1") (pintype "passive"))
    )
    (net (code "129") (name "unconnected-(JP2-Pad2)") (class "Default")
      (node (ref "JP2") (pin "2") (pinfunction "2_2") (pintype "passive"))
    )
    (net (code "130") (name "unconnected-(JP2-Pad3)") (class "Default")
      (node (ref "JP2") (pin "3") (pinfunction "3_3") (pintype "passive"))
    )
    (net (code "131") (name "unconnected-(JP2-Pad4)") (class "Default")
      (node (ref "JP2") (pin "4") (pinfunction "4_4") (pintype "passive"))
    )
    (net (code "132") (name "unconnected-(JP2-Pad7)") (class "Default")
      (node (ref "JP2") (pin "7") (pinfunction "7_7") (pintype "passive"))
    )
    (net (code "133") (name "unconnected-(JP2-Pad8)") (class "Default")
      (node (ref "JP2") (pin "8") (pinfunction "8_8") (pintype "passive"))
    )
    (net (code "134") (name "unconnected-(JP2-Pad9)") (class "Default")
      (node (ref "JP2") (pin "9") (pinfunction "9_9") (pintype "passive"))
    )
    (net (code "135") (name "unconnected-(JP2-Pad10)") (class "Default")
      (node (ref "JP2") (pin "10") (pinfunction "10_10") (pintype "passive"))
    )
    (net (code "136") (name "unconnected-(JP2-Pad11)") (class "Default")
      (node (ref "JP2") (pin "11") (pinfunction "11_11") (pintype "passive"))
    )
    (net (code "137") (name "unconnected-(JP2-Pad12)") (class "Default")
      (node (ref "JP2") (pin "12") (pinfunction "12_12") (pintype "passive"))
    )
    (net (code "138") (name "unconnected-(JP2-Pad13)") (class "Default")
      (node (ref "JP2") (pin "13") (pinfunction "13_13") (pintype "passive"))
    )
    (net (code "139") (name "unconnected-(JP2-Pad14)") (class "Default")
      (node (ref "JP2") (pin "14") (pinfunction "14_14") (pintype "passive"))
    )
    (net (code "140") (name "unconnected-(JP2-Pad15)") (class "Default")
      (node (ref "JP2") (pin "15") (pinfunction "15_15") (pintype "passive"))
    )
    (net (code "141") (name "unconnected-(JP2-Pad16)") (class "Default")
      (node (ref "JP2") (pin "16") (pinfunction "16_16") (pintype "passive"))
    )
    (net (code "142") (name "unconnected-(JP2-Pad17)") (class "Default")
      (node (ref "JP2") (pin "17") (pinfunction "17_17") (pintype "passive"))
    )
    (net (code "143") (name "unconnected-(JP2-Pad18)") (class "Default")
      (node (ref "JP2") (pin "18") (pinfunction "18_18") (pintype "passive"))
    )
    (net (code "144") (name "unconnected-(JP2-Pad19)") (class "Default")
      (node (ref "JP2") (pin "19") (pinfunction "19_19") (pintype "passive"))
    )
    (net (code "145") (name "unconnected-(JP2-Pad20)") (class "Default")
      (node (ref "JP2") (pin "20") (pinfunction "20_20") (pintype "passive"))
    )
    (net (code "146") (name "unconnected-(JP2-Pad21)") (class "Default")
      (node (ref "JP2") (pin "21") (pinfunction "21_21") (pintype "passive"))
    )
    (net (code "147") (name "unconnected-(JP2-Pad22)") (class "Default")
      (node (ref "JP2") (pin "22") (pinfunction "22_22") (pintype "passive"))
    )
    (net (code "148") (name "unconnected-(JP2-Pad23)") (class "Default")
      (node (ref "JP2") (pin "23") (pinfunction "23_23") (pintype "passive"))
    )
    (net (code "149") (name "unconnected-(JP2-Pad24)") (class "Default")
      (node (ref "JP2") (pin "24") (pinfunction "24_24") (pintype "passive"))
    )
    (net (code "150") (name "unconnected-(JP2-Pad25)") (class "Default")
      (node (ref "JP2") (pin "25") (pinfunction "25_25") (pintype "passive"))
    )
    (net (code "151") (name "unconnected-(JP2-Pad28)") (class "Default")
      (node (ref "JP2") (pin "28") (pinfunction "28_28") (pintype "passive"))
    )
    (net (code "152") (name "unconnected-(JP2-Pad29)") (class "Default")
      (node (ref "JP2") (pin "29") (pinfunction "29_29") (pintype "passive"))
    )
    (net (code "153") (name "unconnected-(JP2-Pad30)") (class "Default")
      (node (ref "JP2") (pin "30") (pinfunction "30_30") (pintype "passive"))
    )
    (net (code "154") (name "unconnected-(JP2-Pad31)") (class "Default")
      (node (ref "JP2") (pin "31") (pinfunction "31_31") (pintype "passive"))
    )
    (net (code "155") (name "unconnected-(JP2-Pad32)") (class "Default")
      (node (ref "JP2") (pin "32") (pinfunction "32_32") (pintype "passive"))
    )
    (net (code "156") (name "unconnected-(JP2-Pad35)") (class "Default")
      (node (ref "JP2") (pin "35") (pinfunction "35_35") (pintype "passive"))
    )
    (net (code "157") (name "unconnected-(JP2-Pad40)") (class "Default")
      (node (ref "JP2") (pin "40") (pinfunction "40_40") (pintype "passive"))
    )
    (net (code "158") (name "unconnected-(JP2-Pad41)") (class "Default")
      (node (ref "JP2") (pin "41") (pinfunction "41_41") (pintype "passive"))
    )
    (net (code "159") (name "unconnected-(JP2-Pad42)") (class "Default")
      (node (ref "JP2") (pin "42") (pinfunction "42_42") (pintype "passive"))
    )
    (net (code "160") (name "unconnected-(JP2-Pad43)") (class "Default")
      (node (ref "JP2") (pin "43") (pinfunction "43_43") (pintype "passive"))
    )
    (net (code "161") (name "unconnected-(JP2-Pad44)") (class "Default")
      (node (ref "JP2") (pin "44") (pinfunction "44_44") (pintype "passive"))
    )
    (net (code "162") (name "unconnected-(JP2-Pad45)") (class "Default")
      (node (ref "JP2") (pin "45") (pinfunction "45_45") (pintype "passive"))
    )
    (net (code "163") (name "unconnected-(JP2-Pad46)") (class "Default")
      (node (ref "JP2") (pin "46") (pinfunction "46_46") (pintype "passive"))
    )
    (net (code "164") (name "unconnected-(JP2-Pad47)") (class "Default")
      (node (ref "JP2") (pin "47") (pinfunction "47_47") (pintype "passive"))
    )
    (net (code "165") (name "unconnected-(JP2-Pad48)") (class "Default")
      (node (ref "JP2") (pin "48") (pinfunction "48_48") (pintype "passive"))
    )
    (net (code "166") (name "unconnected-(JP2-Pad49)") (class "Default")
      (node (ref "JP2") (pin "49") (pinfunction "49_49") (pintype "passive"))
    )
    (net (code "167") (name "unconnected-(JP2-Pad50)") (class "Default")
      (node (ref "JP2") (pin "50") (pinfunction "50_50") (pintype "passive"))
    )
    (net (code "168") (name "unconnected-(JP2-Pad51)") (class "Default")
      (node (ref "JP2") (pin "51") (pinfunction "51_51") (pintype "passive"))
    )
    (net (code "169") (name "unconnected-(JP2-Pad52)") (class "Default")
      (node (ref "JP2") (pin "52") (pinfunction "52_52") (pintype "passive"))
    )
    (net (code "170") (name "unconnected-(JP2-Pad53)") (class "Default")
      (node (ref "JP2") (pin "53") (pinfunction "53_53") (pintype "passive"))
    )
    (net (code "171") (name "unconnected-(JP2-Pad54)") (class "Default")
      (node (ref "JP2") (pin "54") (pinfunction "54_54") (pintype "passive"))
    )
    (net (code "172") (name "unconnected-(JP2-Pad59)") (class "Default")
      (node (ref "JP2") (pin "59") (pinfunction "59_59") (pintype "passive"))
    )
    (net (code "173") (name "unconnected-(JP2-Pad60)") (class "Default")
      (node (ref "JP2") (pin "60") (pinfunction "60_60") (pintype "passive"))
    )
  )
)
